# UNO-TH_Rev3e.net
KiCad netlist of a schematic drawn in Altium Designer
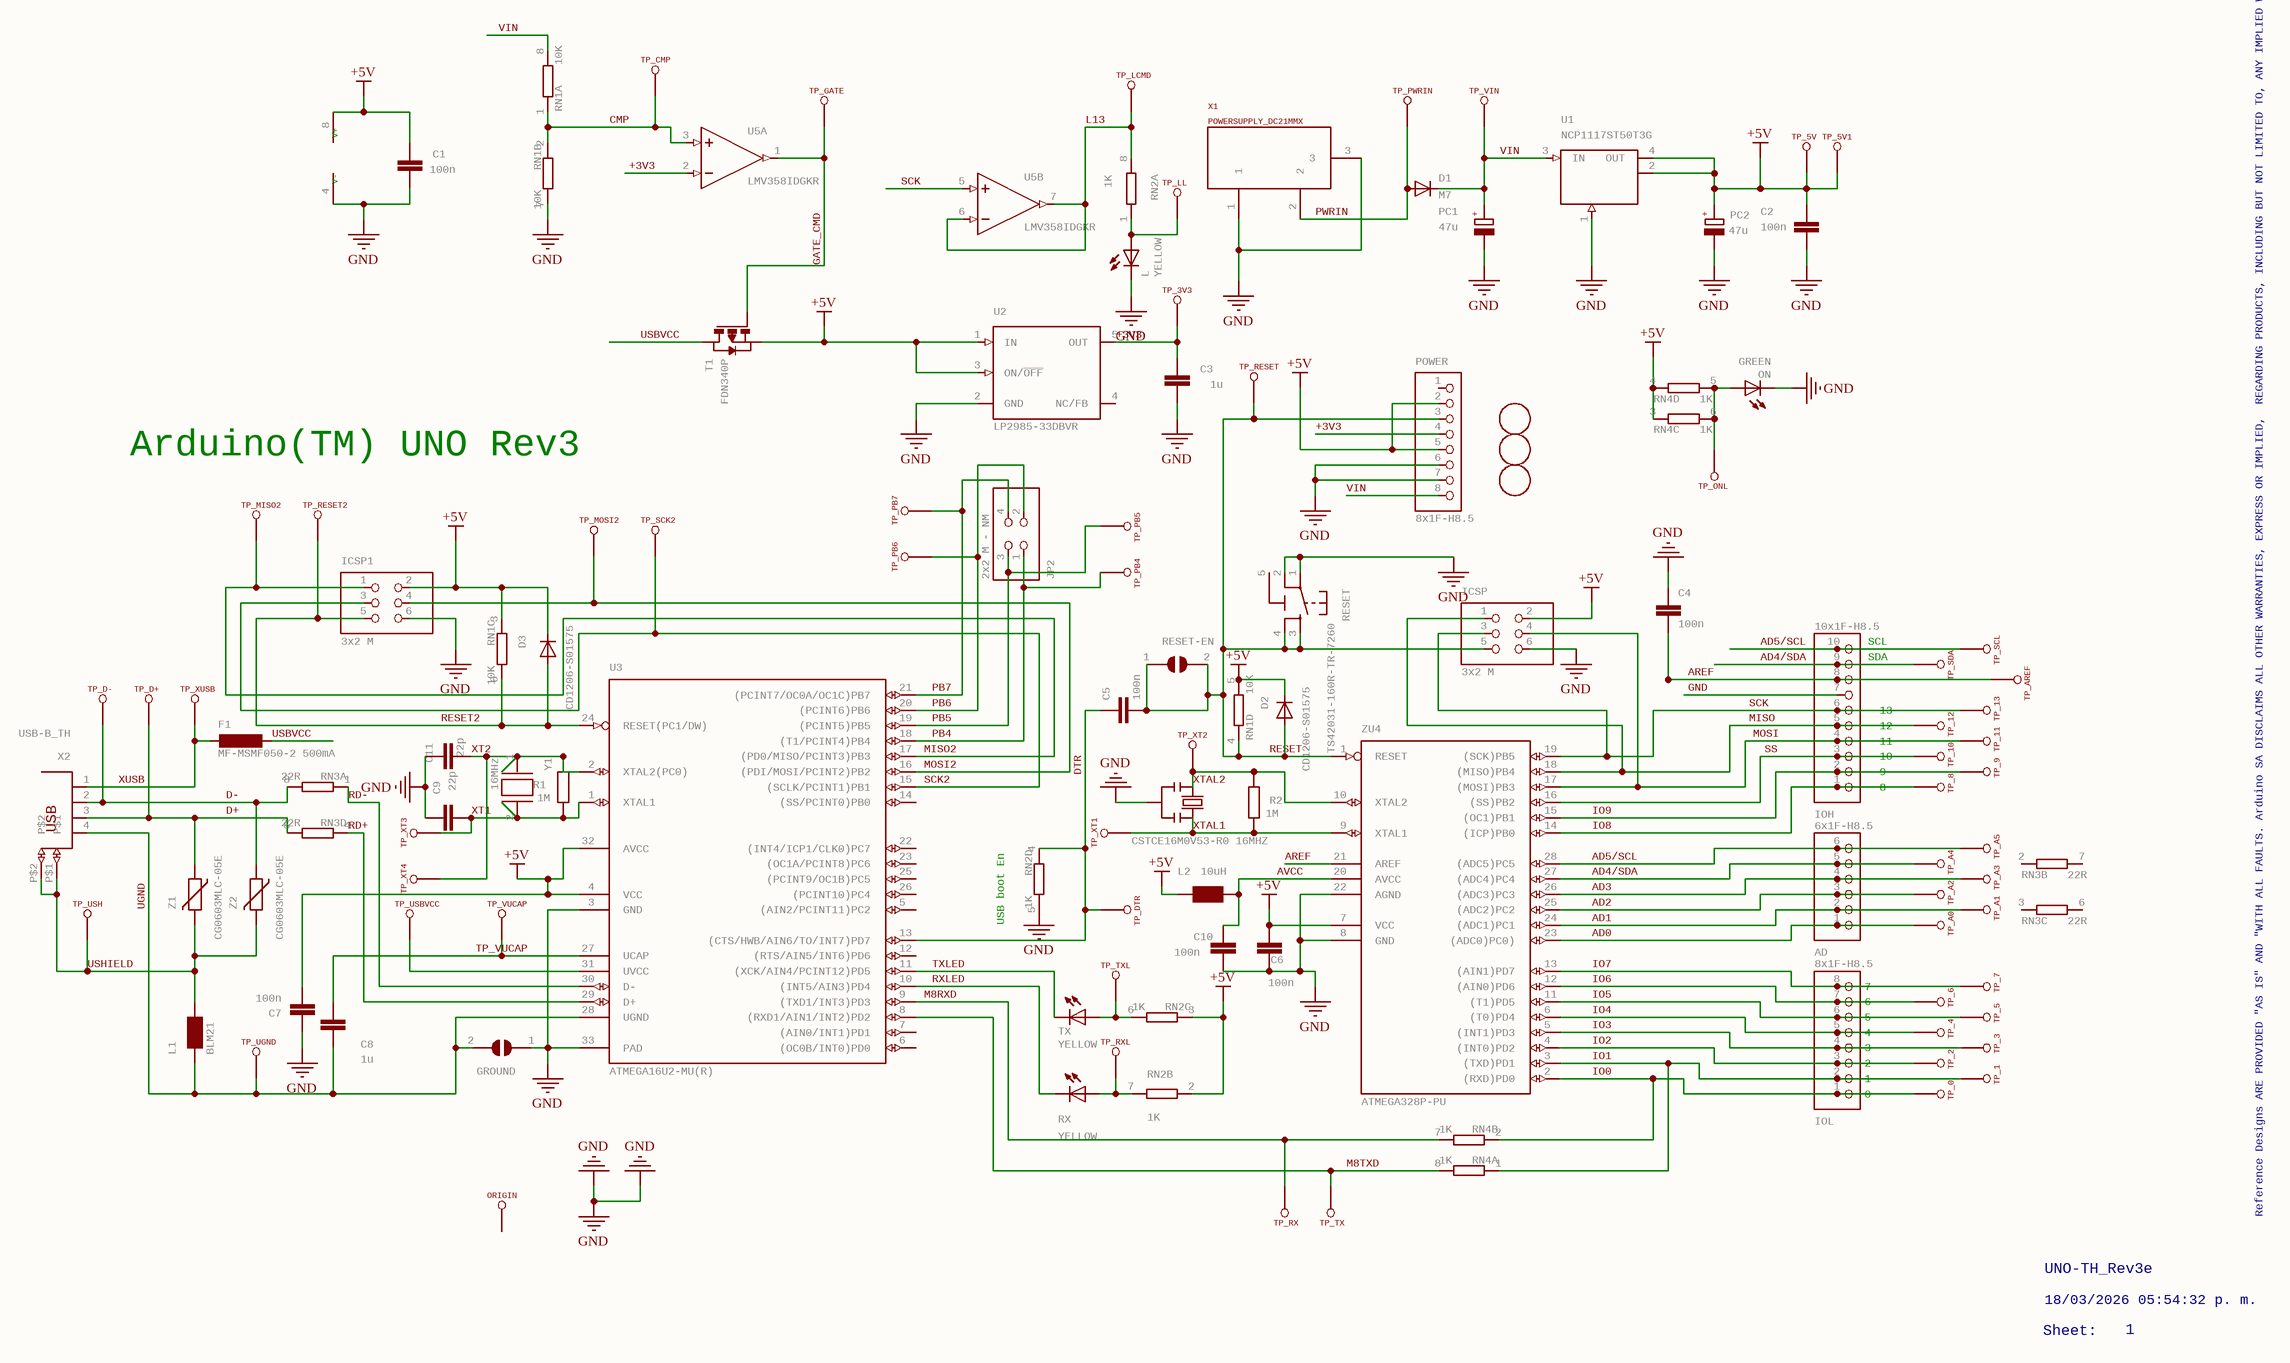
[diagram p0: UNO-TH_Rev3e.SchDoc]

(export (version "E")
  (design (tool "Eeschema 10.0.6"))
  (components
    (comp (ref "AD")
      (value "6x1F-H8.5")
      (footprint "1X06")
      (description "PIN HEADER")
      (libsource (lib "SmartPrj") (part "PINHD-1X6"))
    )
    (comp (ref "C1")
      (value "100n")
      (footprint "C0603-ROUND")
      (description "CAPACITOR, European symbol")
      (libsource (lib "") (part "C-EU0603-RND_2"))
    )
    (comp (ref "C2")
      (value "100n")
      (footprint "C0603-ROUND")
      (description "CAPACITOR, European symbol")
      (libsource (lib "") (part "C-EU0603-RND_1"))
    )
    (comp (ref "C3")
      (value "1u")
      (footprint "C0603-ROUND")
      (description "CAPACITOR, European symbol")
      (libsource (lib "") (part "C-EU0603-RND_2"))
    )
    (comp (ref "C4")
      (value "100n")
      (footprint "C0603-ROUND")
      (description "CAPACITOR, European symbol")
      (libsource (lib "SmartPrj") (part "C-EU0603-RND"))
    )
    (comp (ref "C5")
      (value "100n")
      (footprint "C0603-ROUND")
      (description "CAPACITOR, European symbol")
      (libsource (lib "") (part "C-EU0603-RND_2"))
    )
    (comp (ref "C6")
      (value "100n")
      (footprint "C0603-ROUND")
      (description "CAPACITOR, European symbol")
      (libsource (lib "") (part "C-EU0603-RND_1"))
    )
    (comp (ref "C7")
      (value "100n")
      (footprint "C0603-ROUND")
      (description "CAPACITOR, European symbol")
      (libsource (lib "") (part "C-EU0603-RND_3"))
    )
    (comp (ref "C8")
      (value "1u")
      (footprint "C0603-ROUND")
      (description "CAPACITOR, European symbol")
      (libsource (lib "") (part "C-EU0603-RND_3"))
    )
    (comp (ref "C9")
      (value "22p")
      (footprint "C0603-ROUND")
      (description "CAPACITOR, European symbol")
      (libsource (lib "SmartPrj") (part "C-EU0603-RND"))
    )
    (comp (ref "C10")
      (value "100n")
      (footprint "C0603-ROUND")
      (description "CAPACITOR, European symbol")
      (libsource (lib "") (part "C-EU0603-RND_1"))
    )
    (comp (ref "C11")
      (value "22p")
      (footprint "C0603-ROUND")
      (description "CAPACITOR, European symbol")
      (libsource (lib "SmartPrj") (part "C-EU0603-RND"))
    )
    (comp (ref "D1")
      (value "M7")
      (footprint "SMB")
      (description "DIODE")
      (libsource (lib "diode") (part "DIODE-SMB"))
    )
    (comp (ref "D2")
      (value "CD1206-S01575")
      (footprint "MINIMELF")
      (description "DIODE")
      (libsource (lib "diode") (part "DIODE-MINIMELF"))
    )
    (comp (ref "D3")
      (value "CD1206-S01575")
      (footprint "MINIMELF")
      (description "DIODE")
      (libsource (lib "diode") (part "DIODE-MINIMELF"))
    )
    (comp (ref "F1")
      (value "MF-MSMF050-2 500mA")
      (footprint "L1812")
      (description "INDUCTOR, European symbol")
      (libsource (lib "rcl") (part "L-EUL1812"))
    )
    (comp (ref "FD1")
      (value "FIDUCIALMOUNT")
      (footprint "FIDUCIA-MOUNT")
      (libsource (lib "SmartPrj") (part "FIDUCIALMOUNT"))
    )
    (comp (ref "FD2")
      (value "FIDUCIALMOUNT")
      (footprint "FIDUCIA-MOUNT")
      (libsource (lib "SmartPrj") (part "FIDUCIALMOUNT"))
    )
    (comp (ref "FD3")
      (value "FIDUCIALMOUNT")
      (footprint "FIDUCIA-MOUNT")
      (libsource (lib "SmartPrj") (part "FIDUCIALMOUNT"))
    )
    (comp (ref "GROUND")
      (value "SJ")
      (footprint "SJ")
      (description "SMD solder JUMPER")
      (libsource (lib "jumper") (part "SJ"))
    )
    (comp (ref "ICSP")
      (value "3x2 M")
      (footprint "2X03")
      (description "PIN HEADER")
      (libsource (lib "SmartPrj") (part "PINHD-2X3"))
    )
    (comp (ref "ICSP1")
      (value "3x2 M")
      (footprint "2X03")
      (description "PIN HEADER")
      (libsource (lib "SmartPrj") (part "PINHD-2X3"))
    )
    (comp (ref "IOH")
      (value "10x1F-H8.5")
      (footprint "1X10")
      (description "PIN HEADER")
      (libsource (lib "SmartPrj") (part "PINHD-1X10_ARD"))
    )
    (comp (ref "IOL")
      (value "8x1F-H8.5")
      (footprint "1X08")
      (description "PIN HEADER")
      (libsource (lib "SmartPrj") (part "PINHD-1X8"))
    )
    (comp (ref "JP2")
      (value "2x2 M - NM")
      (footprint "2X02")
      (description "PIN HEADER")
      (libsource (lib "SmartPrj") (part "PINHD-2X2"))
    )
    (comp (ref "L")
      (value "YELLOW")
      (footprint "CHIP-LED0805")
      (libsource (lib "led") (part "LEDCHIP-LED0805"))
    )
    (comp (ref "L1")
      (value "BLM21")
      (footprint "0805")
      (libsource (lib "wuerth-elektronik") (part "WE-CBF_0805"))
    )
    (comp (ref "L2")
      (value "10uH")
      (footprint "0805")
      (description "10uH 0805")
      (fields (field (name "PART_NUMBER") "CV201210-100K"))
      (libsource (lib "Induttanze") (part "0715_CV201210-100K"))
    )
    (comp (ref "ON")
      (value "GREEN")
      (footprint "CHIP-LED0805")
      (libsource (lib "led") (part "LEDCHIP-LED0805"))
    )
    (comp (ref "ORIGIN") (value "TP_SP") (footprint "TP-SP") (libsource (lib "SmartPrj") (part "TP_SP")))
    (comp (ref "PC1")
      (value "47u")
      (footprint "PANASONIC_D")
      (description "POLARIZED CAPACITOR, European symbol")
      (fields (field (name "+") "+"))
      (libsource (lib "rcl") (part "CPOL-EUD"))
    )
    (comp (ref "PC2")
      (value "47u")
      (footprint "PANASONIC_D")
      (description "POLARIZED CAPACITOR, European symbol")
      (fields (field (name "+") "+"))
      (libsource (lib "rcl") (part "CPOL-EUD"))
    )
    (comp (ref "POWER")
      (value "8x1F-H8.5")
      (footprint "1X08")
      (description "PIN HEADER")
      (libsource (lib "SmartPrj") (part "PINHD-1X8"))
    )
    (comp (ref "R1")
      (value "1M")
      (footprint "R0603-ROUND")
      (description "RESISTOR, European symbol")
      (libsource (lib "SmartPrj") (part "R-EU_R0603"))
    )
    (comp (ref "R2")
      (value "1M")
      (footprint "R0603-ROUND")
      (description "RESISTOR, European symbol")
      (libsource (lib "SmartPrj") (part "R-EU_R0603"))
    )
    (comp (ref "RESET")
      (value "TS42031-160R-TR-7260")
      (footprint "TS42")
      (description "TS42 Dongnan Electronics Tact switch VDC 12V - 50mA")
      (libsource (lib "SmartPrj") (part "TS42"))
    )
    (comp (ref "RESET-EN")
      (value "SJ")
      (footprint "SJ")
      (description "SMD solder JUMPER")
      (libsource (lib "jumper") (part "SJ"))
    )
    (comp (ref "RN1")
      (value "10K")
      (footprint "CAY16")
      (description "Array Chip Resistor   Source: RS Component / Phycomp")
      (libsource (lib "resistor-dil") (part "4R-NCAY16"))
    )
    (comp (ref "RN2")
      (value "1K")
      (footprint "CAY16")
      (description "Array Chip Resistor   Source: RS Component / Phycomp")
      (libsource (lib "resistor-dil") (part "4R-NCAY16"))
    )
    (comp (ref "RN3")
      (value "22R")
      (footprint "CAY16")
      (description "Array Chip Resistor   Source: RS Component / Phycomp")
      (libsource (lib "resistor-dil") (part "4R-NCAY16"))
    )
    (comp (ref "RN4")
      (value "1K")
      (footprint "CAY16")
      (description "Array Chip Resistor   Source: RS Component / Phycomp")
      (libsource (lib "resistor-dil") (part "4R-NCAY16"))
    )
    (comp (ref "RX")
      (value "YELLOW")
      (footprint "CHIP-LED0805")
      (libsource (lib "led") (part "LEDCHIP-LED0805"))
    )
    (comp (ref "T1")
      (value "FDN340P")
      (footprint "SOT-23")
      (description "MOS FET")
      (libsource (lib "zetex") (part "PMOSSOT23"))
    )
    (comp (ref "TP_0") (value "TP_SP") (footprint "TP-SP") (libsource (lib "SmartPrj") (part "TP_SP")))
    (comp (ref "TP_1") (value "TP_SP") (footprint "TP-SP") (libsource (lib "SmartPrj") (part "TP_SP")))
    (comp (ref "TP_2") (value "TP_SP") (footprint "TP-SP") (libsource (lib "SmartPrj") (part "TP_SP")))
    (comp (ref "TP_3") (value "TP_SP") (footprint "TP-SP") (libsource (lib "SmartPrj") (part "TP_SP")))
    (comp (ref "TP_3V3") (value "TP_SP") (footprint "TP-SP") (libsource (lib "SmartPrj") (part "TP_SP")))
    (comp (ref "TP_4") (value "TP_SP") (footprint "TP-SP") (libsource (lib "SmartPrj") (part "TP_SP")))
    (comp (ref "TP_5") (value "TP_SP") (footprint "TP-SP") (libsource (lib "SmartPrj") (part "TP_SP")))
    (comp (ref "TP_5V") (value "TP_SP") (footprint "TP-SP") (libsource (lib "SmartPrj") (part "TP_SP")))
    (comp (ref "TP_5V1") (value "TP_SP") (footprint "TP-SP") (libsource (lib "SmartPrj") (part "TP_SP")))
    (comp (ref "TP_6") (value "TP_SP") (footprint "TP-SP") (libsource (lib "SmartPrj") (part "TP_SP")))
    (comp (ref "TP_7") (value "TP_SP") (footprint "TP-SP") (libsource (lib "SmartPrj") (part "TP_SP")))
    (comp (ref "TP_8") (value "TP_SP") (footprint "TP-SP") (libsource (lib "SmartPrj") (part "TP_SP")))
    (comp (ref "TP_9") (value "TP_SP") (footprint "TP-SP") (libsource (lib "SmartPrj") (part "TP_SP")))
    (comp (ref "TP_10") (value "TP_SP") (footprint "TP-SP") (libsource (lib "SmartPrj") (part "TP_SP")))
    (comp (ref "TP_11") (value "TP_SP") (footprint "TP-SP") (libsource (lib "SmartPrj") (part "TP_SP")))
    (comp (ref "TP_12") (value "TP_SP") (footprint "TP-SP") (libsource (lib "SmartPrj") (part "TP_SP")))
    (comp (ref "TP_13") (value "TP_SP") (footprint "TP-SP") (libsource (lib "SmartPrj") (part "TP_SP")))
    (comp (ref "TP_A0") (value "TP_SP") (footprint "TP-SP") (libsource (lib "SmartPrj") (part "TP_SP")))
    (comp (ref "TP_A1") (value "TP_SP") (footprint "TP-SP") (libsource (lib "SmartPrj") (part "TP_SP")))
    (comp (ref "TP_A2") (value "TP_SP") (footprint "TP-SP") (libsource (lib "SmartPrj") (part "TP_SP")))
    (comp (ref "TP_A3") (value "TP_SP") (footprint "TP-SP") (libsource (lib "SmartPrj") (part "TP_SP")))
    (comp (ref "TP_A4") (value "TP_SP") (footprint "TP-SP") (libsource (lib "SmartPrj") (part "TP_SP")))
    (comp (ref "TP_A5") (value "TP_SP") (footprint "TP-SP") (libsource (lib "SmartPrj") (part "TP_SP")))
    (comp (ref "TP_AREF") (value "TP_SP") (footprint "TP-SP") (libsource (lib "SmartPrj") (part "TP_SP")))
    (comp (ref "TP_CMP") (value "TP_SP") (footprint "TP-SP") (libsource (lib "SmartPrj") (part "TP_SP")))
    (comp (ref "TP_D+") (value "TP_SP") (footprint "TP-SP") (libsource (lib "SmartPrj") (part "TP_SP")))
    (comp (ref "TP_D-") (value "TP_SP") (footprint "TP-SP") (libsource (lib "SmartPrj") (part "TP_SP")))
    (comp (ref "TP_DTR") (value "TP_SP") (footprint "TP-SP") (libsource (lib "SmartPrj") (part "TP_SP")))
    (comp (ref "TP_GATE") (value "TP_SP") (footprint "TP-SP") (libsource (lib "SmartPrj") (part "TP_SP")))
    (comp (ref "TP_LCMD") (value "TP_SP") (footprint "TP-SP") (libsource (lib "SmartPrj") (part "TP_SP")))
    (comp (ref "TP_LL") (value "TP_SP") (footprint "TP-SP") (libsource (lib "SmartPrj") (part "TP_SP")))
    (comp (ref "TP_MISO2") (value "TP_SP") (footprint "TP-SP") (libsource (lib "SmartPrj") (part "TP_SP")))
    (comp (ref "TP_MOSI2") (value "TP_SP") (footprint "TP-SP") (libsource (lib "SmartPrj") (part "TP_SP")))
    (comp (ref "TP_ONL") (value "TP_SP") (footprint "TP-SP") (libsource (lib "SmartPrj") (part "TP_SP")))
    (comp (ref "TP_PB4") (value "TP_SP") (footprint "TP-SP") (libsource (lib "SmartPrj") (part "TP_SP")))
    (comp (ref "TP_PB5") (value "TP_SP") (footprint "TP-SP") (libsource (lib "SmartPrj") (part "TP_SP")))
    (comp (ref "TP_PB6") (value "TP_SP") (footprint "TP-SP") (libsource (lib "SmartPrj") (part "TP_SP")))
    (comp (ref "TP_PB7") (value "TP_SP") (footprint "TP-SP") (libsource (lib "SmartPrj") (part "TP_SP")))
    (comp (ref "TP_PWRIN") (value "TP_SP") (footprint "TP-SP") (libsource (lib "SmartPrj") (part "TP_SP")))
    (comp (ref "TP_RESET") (value "TP_SP") (footprint "TP-SP") (libsource (lib "SmartPrj") (part "TP_SP")))
    (comp (ref "TP_RESET2") (value "TP_SP") (footprint "TP-SP") (libsource (lib "SmartPrj") (part "TP_SP")))
    (comp (ref "TP_RX") (value "TP_SP") (footprint "TP-SP") (libsource (lib "SmartPrj") (part "TP_SP")))
    (comp (ref "TP_RXL") (value "TP_SP") (footprint "TP-SP") (libsource (lib "SmartPrj") (part "TP_SP")))
    (comp (ref "TP_SCK2") (value "TP_SP") (footprint "TP-SP") (libsource (lib "SmartPrj") (part "TP_SP")))
    (comp (ref "TP_SCL") (value "TP_SP") (footprint "TP-SP") (libsource (lib "SmartPrj") (part "TP_SP")))
    (comp (ref "TP_SDA") (value "TP_SP") (footprint "TP-SP") (libsource (lib "SmartPrj") (part "TP_SP")))
    (comp (ref "TP_TX") (value "TP_SP") (footprint "TP-SP") (libsource (lib "SmartPrj") (part "TP_SP")))
    (comp (ref "TP_TXL") (value "TP_SP") (footprint "TP-SP") (libsource (lib "SmartPrj") (part "TP_SP")))
    (comp (ref "TP_UGND") (value "TP_SP") (footprint "TP-SP") (libsource (lib "SmartPrj") (part "TP_SP")))
    (comp (ref "TP_USBVCC") (value "TP_SP") (footprint "TP-SP") (libsource (lib "SmartPrj") (part "TP_SP")))
    (comp (ref "TP_USH") (value "TP_SP") (footprint "TP-SP") (libsource (lib "SmartPrj") (part "TP_SP")))
    (comp (ref "TP_VIN") (value "TP_SP") (footprint "TP-SP") (libsource (lib "SmartPrj") (part "TP_SP")))
    (comp (ref "TP_VUCAP") (value "TP_SP") (footprint "TP-SP") (libsource (lib "SmartPrj") (part "TP_SP")))
    (comp (ref "TP_XT1") (value "TP_SP") (footprint "TP-SP") (libsource (lib "SmartPrj") (part "TP_SP")))
    (comp (ref "TP_XT2") (value "TP_SP") (footprint "TP-SP") (libsource (lib "SmartPrj") (part "TP_SP")))
    (comp (ref "TP_XT3") (value "TP_SP") (footprint "TP-SP") (libsource (lib "SmartPrj") (part "TP_SP")))
    (comp (ref "TP_XT4") (value "TP_SP") (footprint "TP-SP") (libsource (lib "SmartPrj") (part "TP_SP")))
    (comp (ref "TP_XUSB") (value "TP_SP") (footprint "TP-SP") (libsource (lib "SmartPrj") (part "TP_SP")))
    (comp (ref "TX")
      (value "YELLOW")
      (footprint "CHIP-LED0805")
      (libsource (lib "led") (part "LEDCHIP-LED0805"))
    )
    (comp (ref "U1")
      (value "NCP1117ST50T3G")
      (footprint "SOT223")
      (libsource (lib "linear") (part "MC33269ST*"))
    )
    (comp (ref "U2")
      (value "LP2985-33DBVR")
      (footprint "SOT23-DBV")
      (libsource (lib "SmartPrj") (part "LP2985-XXDBVR"))
    )
    (comp (ref "U3")
      (value "ATMEGA16U2-MU(R)")
      (footprint "MLF32")
      (libsource (lib "SmartPrj") (part "ATMEGA16U2-MU"))
    )
    (comp (ref "U5")
      (value "LMV358IDGKR")
      (footprint "MSOP08")
      (fields (field (name "V+") "V+") (field (name "V-") "V-"))
      (libsource (lib "linear") (part "LMV358?*MM"))
    )
    (comp (ref "X1")
      (value "POWERSUPPLY_DC21MMX")
      (footprint "POWERSUPPLY_DC-21MM")
      (libsource (lib "SmartPrj") (part "POWERSUPPLY_DC21MMX"))
    )
    (comp (ref "X2")
      (value "USB-B_TH")
      (footprint "PN61729")
      (description "BERG USB connector")
      (fields (field (name "USB") "USB"))
      (libsource (lib "SmartPrj") (part "PN61729"))
    )
    (comp (ref "Y1")
      (value "16MHz")
      (footprint "QS")
      (description "CRYSTAL")
      (libsource (lib "SmartPrj") (part "XTAL/S"))
    )
    (comp (ref "Y2")
      (value "CSTCE16M0V53-R0 16MHZ")
      (footprint "RESONATOR")
      (libsource (lib "SmartPrj") (part "RESONATORMU"))
    )
    (comp (ref "Z1")
      (value "CG0603MLC-05E")
      (footprint "CT/CN0603")
      (description "VARISTOR")
      (libsource (lib "varistor") (part "VARISTORCN0603"))
    )
    (comp (ref "Z2")
      (value "CG0603MLC-05E")
      (footprint "CT/CN0603")
      (description "VARISTOR")
      (libsource (lib "varistor") (part "VARISTORCN0603"))
    )
    (comp (ref "ZU4")
      (value "ATMEGA328P-PU")
      (footprint "DIL28-3")
      (description "MICROCONTROLLER   4 Kbytes FLASH   128 bytes SRAM   256 bytes EEPROM   UART   6-channel 10 bit ADC")
      (libsource (lib "SmartPrj") (part "ATMEGA328P-PU"))
    )
  )
  (nets
    (net (code "1") (name "+5V") (class "Default")
      (node (ref "C1") (pin "2") (pinfunction "2_2") (pintype "passive"))
      (node (ref "C2") (pin "2") (pinfunction "2_2") (pintype "passive"))
      (node (ref "C6") (pin "2") (pinfunction "2_2") (pintype "passive"))
      (node (ref "C7") (pin "1") (pinfunction "1_1") (pintype "passive"))
      (node (ref "D2") (pin "C") (pinfunction "C_C") (pintype "passive"))
      (node (ref "D3") (pin "C") (pinfunction "C_C") (pintype "passive"))
      (node (ref "ICSP") (pin "2") (pinfunction "2_2") (pintype "passive"))
      (node (ref "ICSP1") (pin "2") (pinfunction "2_2") (pintype "passive"))
      (node (ref "L2") (pin "1") (pinfunction "1_1") (pintype "passive"))
      (node (ref "PC2") (pin "+") (pinfunction "+_+") (pintype "passive"))
      (node (ref "POWER") (pin "2") (pinfunction "2_2") (pintype "passive"))
      (node (ref "POWER") (pin "5") (pinfunction "5_5") (pintype "passive"))
      (node (ref "RN1") (pin "3") (pinfunction "1_3") (pintype "passive"))
      (node (ref "RN1") (pin "5") (pinfunction "2_5") (pintype "passive"))
      (node (ref "RN2") (pin "2") (pinfunction "1_2") (pintype "passive"))
      (node (ref "RN2") (pin "3") (pinfunction "1_3") (pintype "passive"))
      (node (ref "RN4") (pin "3") (pinfunction "1_3") (pintype "passive"))
      (node (ref "RN4") (pin "4") (pinfunction "1_4") (pintype "passive"))
      (node (ref "T1") (pin "2") (pinfunction "S_2") (pintype "passive"))
      (node (ref "TP_5V") (pin "X") (pinfunction "TESTP_X") (pintype "passive"))
      (node (ref "TP_5V1") (pin "X") (pinfunction "TESTP_X") (pintype "passive"))
      (node (ref "U1") (pin "2") (pinfunction "OUT_2") (pintype "passive"))
      (node (ref "U1") (pin "4") (pinfunction "OUT_4") (pintype "passive"))
      (node (ref "U2") (pin "1") (pinfunction "IN_1") (pintype "input"))
      (node (ref "U2") (pin "3") (pinfunction "ON/~{OFF}_3") (pintype "input"))
      (node (ref "U3") (pin "32") (pinfunction "AVCC_32") (pintype "power_in"))
      (node (ref "U3") (pin "4") (pinfunction "VCC_4") (pintype "power_in"))
      (node (ref "U5") (pin "8") (pinfunction "V+_8") (pintype "power_in"))
      (node (ref "ZU4") (pin "7") (pinfunction "VCC_7") (pintype "power_in"))
    )
    (net (code "2") (name "/+3V3") (class "Default")
      (node (ref "C3") (pin "2") (pinfunction "2_2") (pintype "passive"))
      (node (ref "POWER") (pin "4") (pinfunction "4_4") (pintype "passive"))
      (node (ref "TP_3V3") (pin "X") (pinfunction "TESTP_X") (pintype "passive"))
      (node (ref "U2") (pin "5") (pinfunction "OUT_5") (pintype "passive"))
      (node (ref "U5") (pin "2") (pinfunction "-IN_2") (pintype "input"))
    )
    (net (code "3") (name "/AD0") (class "Default")
      (node (ref "AD") (pin "1") (pinfunction "1_1") (pintype "passive"))
      (node (ref "TP_A0") (pin "X") (pinfunction "TESTP_X") (pintype "passive"))
      (node (ref "ZU4") (pin "23") (pinfunction "(ADC0)PC0)_23") (pintype "bidirectional"))
    )
    (net (code "4") (name "/AD1") (class "Default")
      (node (ref "AD") (pin "2") (pinfunction "2_2") (pintype "passive"))
      (node (ref "TP_A1") (pin "X") (pinfunction "TESTP_X") (pintype "passive"))
      (node (ref "ZU4") (pin "24") (pinfunction "(ADC1)PC1_24") (pintype "bidirectional"))
    )
    (net (code "5") (name "/AD2") (class "Default")
      (node (ref "AD") (pin "3") (pinfunction "3_3") (pintype "passive"))
      (node (ref "TP_A2") (pin "X") (pinfunction "TESTP_X") (pintype "passive"))
      (node (ref "ZU4") (pin "25") (pinfunction "(ADC2)PC2_25") (pintype "bidirectional"))
    )
    (net (code "6") (name "/AD3") (class "Default")
      (node (ref "AD") (pin "4") (pinfunction "4_4") (pintype "passive"))
      (node (ref "TP_A3") (pin "X") (pinfunction "TESTP_X") (pintype "passive"))
      (node (ref "ZU4") (pin "26") (pinfunction "(ADC3)PC3_26") (pintype "bidirectional"))
    )
    (net (code "7") (name "/AD4{slash}SDA") (class "Default")
      (node (ref "AD") (pin "5") (pinfunction "5_5") (pintype "passive"))
      (node (ref "IOH") (pin "9") (pinfunction "9_9") (pintype "passive"))
      (node (ref "TP_A4") (pin "X") (pinfunction "TESTP_X") (pintype "passive"))
      (node (ref "TP_SDA") (pin "X") (pinfunction "TESTP_X") (pintype "passive"))
      (node (ref "ZU4") (pin "27") (pinfunction "(ADC4)PC4_27") (pintype "bidirectional"))
    )
    (net (code "8") (name "/AD5{slash}SCL") (class "Default")
      (node (ref "AD") (pin "6") (pinfunction "6_6") (pintype "passive"))
      (node (ref "IOH") (pin "10") (pinfunction "10_10") (pintype "passive"))
      (node (ref "TP_A5") (pin "X") (pinfunction "TESTP_X") (pintype "passive"))
      (node (ref "TP_SCL") (pin "X") (pinfunction "TESTP_X") (pintype "passive"))
      (node (ref "ZU4") (pin "28") (pinfunction "(ADC5)PC5_28") (pintype "bidirectional"))
    )
    (net (code "9") (name "/AREF") (class "Default")
      (node (ref "C4") (pin "2") (pinfunction "2_2") (pintype "passive"))
      (node (ref "IOH") (pin "8") (pinfunction "8_8") (pintype "passive"))
      (node (ref "TP_AREF") (pin "X") (pinfunction "TESTP_X") (pintype "passive"))
      (node (ref "ZU4") (pin "21") (pinfunction "AREF_21") (pintype "passive"))
    )
    (net (code "10") (name "/AVCC") (class "Default")
      (node (ref "C10") (pin "2") (pinfunction "2_2") (pintype "passive"))
      (node (ref "L2") (pin "2") (pinfunction "2_2") (pintype "passive"))
      (node (ref "ZU4") (pin "20") (pinfunction "AVCC_20") (pintype "power_in"))
    )
    (net (code "11") (name "/CMP") (class "Default")
      (node (ref "RN1") (pin "1") (pinfunction "1_1") (pintype "passive"))
      (node (ref "RN1") (pin "2") (pinfunction "1_2") (pintype "passive"))
      (node (ref "TP_CMP") (pin "X") (pinfunction "TESTP_X") (pintype "passive"))
      (node (ref "U5") (pin "3") (pinfunction "+IN_3") (pintype "input"))
    )
    (net (code "12") (name "/D+") (class "Default")
      (node (ref "RN3") (pin "5") (pinfunction "2_5") (pintype "passive"))
      (node (ref "TP_D+") (pin "X") (pinfunction "TESTP_X") (pintype "passive"))
      (node (ref "X2") (pin "3") (pinfunction "3_3") (pintype "bidirectional"))
      (node (ref "Z1") (pin "1") (pinfunction "1_1") (pintype "passive"))
    )
    (net (code "13") (name "/D-") (class "Default")
      (node (ref "RN3") (pin "8") (pinfunction "2_8") (pintype "passive"))
      (node (ref "TP_D-") (pin "X") (pinfunction "TESTP_X") (pintype "passive"))
      (node (ref "X2") (pin "2") (pinfunction "2_2") (pintype "bidirectional"))
      (node (ref "Z2") (pin "1") (pinfunction "1_1") (pintype "passive"))
    )
    (net (code "14") (name "/DTR") (class "Default")
      (node (ref "C5") (pin "1") (pinfunction "1_1") (pintype "passive"))
      (node (ref "RN2") (pin "4") (pinfunction "1_4") (pintype "passive"))
      (node (ref "TP_DTR") (pin "X") (pinfunction "TESTP_X") (pintype "passive"))
      (node (ref "U3") (pin "13") (pinfunction "(CTS/HWB/AIN6/TO/INT7)PD7_13") (pintype "bidirectional"))
    )
    (net (code "15") (name "/GATE_CMD") (class "Default")
      (node (ref "T1") (pin "3") (pinfunction "G_3") (pintype "passive"))
      (node (ref "TP_GATE") (pin "X") (pinfunction "TESTP_X") (pintype "passive"))
      (node (ref "U5") (pin "1") (pinfunction "OUT_1") (pintype "output"))
    )
    (net (code "16") (name "/IO0") (class "Default")
      (node (ref "IOL") (pin "1") (pinfunction "1_1") (pintype "passive"))
      (node (ref "RN4") (pin "2") (pinfunction "1_2") (pintype "passive"))
      (node (ref "TP_0") (pin "X") (pinfunction "TESTP_X") (pintype "passive"))
      (node (ref "ZU4") (pin "2") (pinfunction "(RXD)PD0_2") (pintype "bidirectional"))
    )
    (net (code "17") (name "/IO1") (class "Default")
      (node (ref "IOL") (pin "2") (pinfunction "2_2") (pintype "passive"))
      (node (ref "RN4") (pin "1") (pinfunction "1_1") (pintype "passive"))
      (node (ref "TP_1") (pin "X") (pinfunction "TESTP_X") (pintype "passive"))
      (node (ref "ZU4") (pin "3") (pinfunction "(TXD)PD1_3") (pintype "bidirectional"))
    )
    (net (code "18") (name "/IO2") (class "Default")
      (node (ref "IOL") (pin "3") (pinfunction "3_3") (pintype "passive"))
      (node (ref "TP_2") (pin "X") (pinfunction "TESTP_X") (pintype "passive"))
      (node (ref "ZU4") (pin "4") (pinfunction "(INT0)PD2_4") (pintype "bidirectional"))
    )
    (net (code "19") (name "/IO3") (class "Default")
      (node (ref "IOL") (pin "4") (pinfunction "4_4") (pintype "passive"))
      (node (ref "TP_3") (pin "X") (pinfunction "TESTP_X") (pintype "passive"))
      (node (ref "ZU4") (pin "5") (pinfunction "(INT1)PD3_5") (pintype "bidirectional"))
    )
    (net (code "20") (name "/IO4") (class "Default")
      (node (ref "IOL") (pin "5") (pinfunction "5_5") (pintype "passive"))
      (node (ref "TP_4") (pin "X") (pinfunction "TESTP_X") (pintype "passive"))
      (node (ref "ZU4") (pin "6") (pinfunction "(T0)PD4_6") (pintype "bidirectional"))
    )
    (net (code "21") (name "/IO5") (class "Default")
      (node (ref "IOL") (pin "6") (pinfunction "6_6") (pintype "passive"))
      (node (ref "TP_5") (pin "X") (pinfunction "TESTP_X") (pintype "passive"))
      (node (ref "ZU4") (pin "11") (pinfunction "(T1)PD5_11") (pintype "bidirectional"))
    )
    (net (code "22") (name "/IO6") (class "Default")
      (node (ref "IOL") (pin "7") (pinfunction "7_7") (pintype "passive"))
      (node (ref "TP_6") (pin "X") (pinfunction "TESTP_X") (pintype "passive"))
      (node (ref "ZU4") (pin "12") (pinfunction "(AIN0)PD6_12") (pintype "bidirectional"))
    )
    (net (code "23") (name "/IO7") (class "Default")
      (node (ref "IOL") (pin "8") (pinfunction "8_8") (pintype "passive"))
      (node (ref "TP_7") (pin "X") (pinfunction "TESTP_X") (pintype "passive"))
      (node (ref "ZU4") (pin "13") (pinfunction "(AIN1)PD7_13") (pintype "bidirectional"))
    )
    (net (code "24") (name "/IO8") (class "Default")
      (node (ref "IOH") (pin "1") (pinfunction "1_1") (pintype "passive"))
      (node (ref "TP_8") (pin "X") (pinfunction "TESTP_X") (pintype "passive"))
      (node (ref "ZU4") (pin "14") (pinfunction "(ICP)PB0_14") (pintype "bidirectional"))
    )
    (net (code "25") (name "/IO9") (class "Default")
      (node (ref "IOH") (pin "2") (pinfunction "2_2") (pintype "passive"))
      (node (ref "TP_9") (pin "X") (pinfunction "TESTP_X") (pintype "passive"))
      (node (ref "ZU4") (pin "15") (pinfunction "(OC1)PB1_15") (pintype "bidirectional"))
    )
    (net (code "26") (name "/L13") (class "Default")
      (node (ref "RN2") (pin "8") (pinfunction "2_8") (pintype "passive"))
      (node (ref "TP_LCMD") (pin "X") (pinfunction "TESTP_X") (pintype "passive"))
      (node (ref "U5") (pin "6") (pinfunction "-IN_6") (pintype "input"))
      (node (ref "U5") (pin "7") (pinfunction "OUT_7") (pintype "output"))
    )
    (net (code "27") (name "/M8RXD") (class "Default")
      (node (ref "RN4") (pin "7") (pinfunction "2_7") (pintype "passive"))
      (node (ref "TP_RX") (pin "X") (pinfunction "TESTP_X") (pintype "passive"))
      (node (ref "U3") (pin "9") (pinfunction "(TXD1/INT3)PD3_9") (pintype "bidirectional"))
    )
    (net (code "28") (name "/M8TXD") (class "Default")
      (node (ref "RN4") (pin "8") (pinfunction "2_8") (pintype "passive"))
      (node (ref "TP_TX") (pin "X") (pinfunction "TESTP_X") (pintype "passive"))
      (node (ref "U3") (pin "8") (pinfunction "(RXD1/AIN1/INT2)PD2_8") (pintype "bidirectional"))
    )
    (net (code "29") (name "/MISO") (class "Default")
      (node (ref "ICSP") (pin "1") (pinfunction "1_1") (pintype "passive"))
      (node (ref "IOH") (pin "5") (pinfunction "5_5") (pintype "passive"))
      (node (ref "TP_12") (pin "X") (pinfunction "TESTP_X") (pintype "passive"))
      (node (ref "ZU4") (pin "18") (pinfunction "(MISO)PB4_18") (pintype "bidirectional"))
    )
    (net (code "30") (name "/MISO2") (class "Default")
      (node (ref "ICSP1") (pin "1") (pinfunction "1_1") (pintype "passive"))
      (node (ref "TP_MISO2") (pin "X") (pinfunction "TESTP_X") (pintype "passive"))
      (node (ref "U3") (pin "17") (pinfunction "(PD0/MISO/PCINT3)PB3_17") (pintype "bidirectional"))
    )
    (net (code "31") (name "/MOSI") (class "Default")
      (node (ref "ICSP") (pin "4") (pinfunction "4_4") (pintype "passive"))
      (node (ref "IOH") (pin "4") (pinfunction "4_4") (pintype "passive"))
      (node (ref "TP_11") (pin "X") (pinfunction "TESTP_X") (pintype "passive"))
      (node (ref "ZU4") (pin "17") (pinfunction "(MOSI)PB3_17") (pintype "bidirectional"))
    )
    (net (code "32") (name "/MOSI2") (class "Default")
      (node (ref "ICSP1") (pin "4") (pinfunction "4_4") (pintype "passive"))
      (node (ref "TP_MOSI2") (pin "X") (pinfunction "TESTP_X") (pintype "passive"))
      (node (ref "U3") (pin "16") (pinfunction "(PDI/MOSI/PCINT2)PB2_16") (pintype "bidirectional"))
    )
    (net (code "33") (name "/PB4") (class "Default")
      (node (ref "JP2") (pin "1") (pinfunction "1_1") (pintype "passive"))
      (node (ref "TP_PB4") (pin "X") (pinfunction "TESTP_X") (pintype "passive"))
      (node (ref "U3") (pin "18") (pinfunction "(T1/PCINT4)PB4_18") (pintype "bidirectional"))
    )
    (net (code "34") (name "/PB5") (class "Default")
      (node (ref "JP2") (pin "3") (pinfunction "3_3") (pintype "passive"))
      (node (ref "TP_PB5") (pin "X") (pinfunction "TESTP_X") (pintype "passive"))
      (node (ref "U3") (pin "19") (pinfunction "(PCINT5)PB5_19") (pintype "bidirectional"))
    )
    (net (code "35") (name "/PB6") (class "Default")
      (node (ref "JP2") (pin "2") (pinfunction "2_2") (pintype "passive"))
      (node (ref "TP_PB6") (pin "X") (pinfunction "TESTP_X") (pintype "passive"))
      (node (ref "U3") (pin "20") (pinfunction "(PCINT6)PB6_20") (pintype "bidirectional"))
    )
    (net (code "36") (name "/PB7") (class "Default")
      (node (ref "JP2") (pin "4") (pinfunction "4_4") (pintype "passive"))
      (node (ref "TP_PB7") (pin "X") (pinfunction "TESTP_X") (pintype "passive"))
      (node (ref "U3") (pin "21") (pinfunction "(PCINT7/OC0A/OC1C)PB7_21") (pintype "bidirectional"))
    )
    (net (code "37") (name "/PWRIN") (class "Default")
      (node (ref "D1") (pin "A") (pinfunction "A_A") (pintype "passive"))
      (node (ref "TP_PWRIN") (pin "X") (pinfunction "TESTP_X") (pintype "passive"))
      (node (ref "X1") (pin "2") (pinfunction "2_2") (pintype "power_in"))
    )
    (net (code "38") (name "/RD+") (class "Default")
      (node (ref "RN3") (pin "4") (pinfunction "1_4") (pintype "passive"))
      (node (ref "U3") (pin "29") (pinfunction "D+_29") (pintype "bidirectional"))
    )
    (net (code "39") (name "/RD-") (class "Default")
      (node (ref "RN3") (pin "1") (pinfunction "1_1") (pintype "passive"))
      (node (ref "U3") (pin "30") (pinfunction "D-_30") (pintype "bidirectional"))
    )
    (net (code "40") (name "/RESET") (class "Default")
      (node (ref "C5") (pin "2") (pinfunction "2_2") (pintype "passive"))
      (node (ref "D2") (pin "A") (pinfunction "A_A") (pintype "passive"))
      (node (ref "ICSP") (pin "5") (pinfunction "5_5") (pintype "passive"))
      (node (ref "POWER") (pin "3") (pinfunction "3_3") (pintype "passive"))
      (node (ref "RESET") (pin "3") (pinfunction "3_3") (pintype "passive"))
      (node (ref "RESET") (pin "4") (pinfunction "4_4") (pintype "passive"))
      (node (ref "RESET-EN") (pin "1") (pinfunction "1_1") (pintype "passive"))
      (node (ref "RESET-EN") (pin "2") (pinfunction "2_2") (pintype "passive"))
      (node (ref "RN1") (pin "4") (pinfunction "1_4") (pintype "passive"))
      (node (ref "TP_RESET") (pin "X") (pinfunction "TESTP_X") (pintype "passive"))
      (node (ref "ZU4") (pin "1") (pinfunction "RESET_1") (pintype "input"))
    )
    (net (code "41") (name "/RESET2") (class "Default")
      (node (ref "D3") (pin "A") (pinfunction "A_A") (pintype "passive"))
      (node (ref "ICSP1") (pin "5") (pinfunction "5_5") (pintype "passive"))
      (node (ref "RN1") (pin "6") (pinfunction "2_6") (pintype "passive"))
      (node (ref "TP_RESET2") (pin "X") (pinfunction "TESTP_X") (pintype "passive"))
      (node (ref "U3") (pin "24") (pinfunction "RESET(PC1/DW)_24") (pintype "input"))
    )
    (net (code "42") (name "/RXLED") (class "Default")
      (node (ref "RX") (pin "C") (pinfunction "C_C") (pintype "passive"))
      (node (ref "U3") (pin "10") (pinfunction "(INT5/AIN3)PD4_10") (pintype "bidirectional"))
    )
    (net (code "43") (name "/SCK") (class "Default")
      (node (ref "ICSP") (pin "3") (pinfunction "3_3") (pintype "passive"))
      (node (ref "IOH") (pin "6") (pinfunction "6_6") (pintype "passive"))
      (node (ref "TP_13") (pin "X") (pinfunction "TESTP_X") (pintype "passive"))
      (node (ref "U5") (pin "5") (pinfunction "+IN_5") (pintype "input"))
      (node (ref "ZU4") (pin "19") (pinfunction "(SCK)PB5_19") (pintype "bidirectional"))
    )
    (net (code "44") (name "/SCK2") (class "Default")
      (node (ref "ICSP1") (pin "3") (pinfunction "3_3") (pintype "passive"))
      (node (ref "TP_SCK2") (pin "X") (pinfunction "TESTP_X") (pintype "passive"))
      (node (ref "U3") (pin "15") (pinfunction "(SCLK/PCINT1)PB1_15") (pintype "bidirectional"))
    )
    (net (code "45") (name "/SS") (class "Default")
      (node (ref "IOH") (pin "3") (pinfunction "3_3") (pintype "passive"))
      (node (ref "TP_10") (pin "X") (pinfunction "TESTP_X") (pintype "passive"))
      (node (ref "ZU4") (pin "16") (pinfunction "(SS)PB2_16") (pintype "bidirectional"))
    )
    (net (code "46") (name "/TP_VUCAP") (class "Default")
      (node (ref "C8") (pin "1") (pinfunction "1_1") (pintype "passive"))
      (node (ref "TP_VUCAP") (pin "X") (pinfunction "TESTP_X") (pintype "passive"))
      (node (ref "U3") (pin "27") (pinfunction "UCAP_27") (pintype "passive"))
    )
    (net (code "47") (name "/TXLED") (class "Default")
      (node (ref "TX") (pin "C") (pinfunction "C_C") (pintype "passive"))
      (node (ref "U3") (pin "11") (pinfunction "(XCK/AIN4/PCINT12)PD5_11") (pintype "bidirectional"))
    )
    (net (code "48") (name "/UGND") (class "Default")
      (node (ref "C8") (pin "2") (pinfunction "2_2") (pintype "passive"))
      (node (ref "GROUND") (pin "2") (pinfunction "2_2") (pintype "passive"))
      (node (ref "L1") (pin "1") (pinfunction "1_1") (pintype "passive"))
      (node (ref "TP_UGND") (pin "X") (pinfunction "TESTP_X") (pintype "passive"))
      (node (ref "U3") (pin "28") (pinfunction "UGND_28") (pintype "power_in"))
      (node (ref "X2") (pin "4") (pinfunction "4_4") (pintype "bidirectional"))
    )
    (net (code "49") (name "/USBVCC") (class "Default")
      (node (ref "F1") (pin "1") (pinfunction "1_1") (pintype "passive"))
      (node (ref "T1") (pin "1") (pinfunction "D_1") (pintype "passive"))
    )
    (net (code "50") (name "/USHIELD") (class "Default")
      (node (ref "L1") (pin "2") (pinfunction "2_2") (pintype "passive"))
      (node (ref "TP_USH") (pin "X") (pinfunction "TESTP_X") (pintype "passive"))
      (node (ref "X2") (pin "P$1") (pinfunction "P$1_P$1") (pintype "bidirectional"))
      (node (ref "X2") (pin "P$2") (pinfunction "P$2_P$2") (pintype "bidirectional"))
      (node (ref "Z1") (pin "2") (pinfunction "2_2") (pintype "passive"))
      (node (ref "Z2") (pin "2") (pinfunction "2_2") (pintype "passive"))
    )
    (net (code "51") (name "/VIN") (class "Default")
      (node (ref "D1") (pin "C") (pinfunction "C_C") (pintype "passive"))
      (node (ref "PC1") (pin "+") (pinfunction "+_+") (pintype "passive"))
      (node (ref "POWER") (pin "8") (pinfunction "8_8") (pintype "passive"))
      (node (ref "RN1") (pin "8") (pinfunction "2_8") (pintype "passive"))
      (node (ref "TP_VIN") (pin "X") (pinfunction "TESTP_X") (pintype "passive"))
      (node (ref "U1") (pin "3") (pinfunction "IN_3") (pintype "input"))
    )
    (net (code "52") (name "/XT1") (class "Default")
      (node (ref "C9") (pin "1") (pinfunction "1_1") (pintype "passive"))
      (node (ref "R1") (pin "1") (pinfunction "1_1") (pintype "passive"))
      (node (ref "TP_XT3") (pin "X") (pinfunction "TESTP_X") (pintype "passive"))
      (node (ref "U3") (pin "1") (pinfunction "XTAL1_1") (pintype "bidirectional"))
      (node (ref "Y1") (pin "2") (pinfunction "2_2") (pintype "passive"))
    )
    (net (code "53") (name "/XT2") (class "Default")
      (node (ref "C11") (pin "1") (pinfunction "1_1") (pintype "passive"))
      (node (ref "R1") (pin "2") (pinfunction "2_2") (pintype "passive"))
      (node (ref "TP_XT4") (pin "X") (pinfunction "TESTP_X") (pintype "passive"))
      (node (ref "U3") (pin "2") (pinfunction "XTAL2(PC0)_2") (pintype "bidirectional"))
      (node (ref "Y1") (pin "1") (pinfunction "1_1") (pintype "passive"))
    )
    (net (code "54") (name "/XTAL1") (class "Default")
      (node (ref "R2") (pin "1") (pinfunction "1_1") (pintype "passive"))
      (node (ref "TP_XT1") (pin "X") (pinfunction "TESTP_X") (pintype "passive"))
      (node (ref "Y2") (pin "3") (pinfunction "3_3") (pintype "passive"))
      (node (ref "ZU4") (pin "9") (pinfunction "XTAL1_9") (pintype "bidirectional"))
    )
    (net (code "55") (name "/XTAL2") (class "Default")
      (node (ref "R2") (pin "2") (pinfunction "2_2") (pintype "passive"))
      (node (ref "TP_XT2") (pin "X") (pinfunction "TESTP_X") (pintype "passive"))
      (node (ref "Y2") (pin "1") (pinfunction "1_1") (pintype "passive"))
      (node (ref "ZU4") (pin "10") (pinfunction "XTAL2_10") (pintype "bidirectional"))
    )
    (net (code "56") (name "/XUSB") (class "Default")
      (node (ref "F1") (pin "2") (pinfunction "2_2") (pintype "passive"))
      (node (ref "TP_XUSB") (pin "X") (pinfunction "TESTP_X") (pintype "passive"))
      (node (ref "X2") (pin "1") (pinfunction "1_1") (pintype "bidirectional"))
    )
    (net (code "57") (name "GND") (class "Default")
      (node (ref "C1") (pin "1") (pinfunction "1_1") (pintype "passive"))
      (node (ref "C10") (pin "1") (pinfunction "1_1") (pintype "passive"))
      (node (ref "C11") (pin "2") (pinfunction "2_2") (pintype "passive"))
      (node (ref "C2") (pin "1") (pinfunction "1_1") (pintype "passive"))
      (node (ref "C3") (pin "1") (pinfunction "1_1") (pintype "passive"))
      (node (ref "C4") (pin "1") (pinfunction "1_1") (pintype "passive"))
      (node (ref "C6") (pin "1") (pinfunction "1_1") (pintype "passive"))
      (node (ref "C7") (pin "2") (pinfunction "2_2") (pintype "passive"))
      (node (ref "C9") (pin "2") (pinfunction "2_2") (pintype "passive"))
      (node (ref "GROUND") (pin "1") (pinfunction "1_1") (pintype "passive"))
      (node (ref "ICSP") (pin "6") (pinfunction "6_6") (pintype "passive"))
      (node (ref "ICSP1") (pin "6") (pinfunction "6_6") (pintype "passive"))
      (node (ref "IOH") (pin "7") (pinfunction "7_7") (pintype "passive"))
      (node (ref "L") (pin "C") (pinfunction "C_C") (pintype "passive"))
      (node (ref "ON") (pin "C") (pinfunction "C_C") (pintype "passive"))
      (node (ref "PC1") (pin "-") (pinfunction "-_-") (pintype "passive"))
      (node (ref "PC2") (pin "-") (pinfunction "-_-") (pintype "passive"))
      (node (ref "POWER") (pin "6") (pinfunction "6_6") (pintype "passive"))
      (node (ref "POWER") (pin "7") (pinfunction "7_7") (pintype "passive"))
      (node (ref "RESET") (pin "1") (pinfunction "1_1") (pintype "passive"))
      (node (ref "RESET") (pin "2") (pinfunction "2_2") (pintype "passive"))
      (node (ref "RN1") (pin "7") (pinfunction "2_7") (pintype "passive"))
      (node (ref "RN2") (pin "5") (pinfunction "2_5") (pintype "passive"))
      (node (ref "U1") (pin "1") (pinfunction "GND/ADJ_1") (pintype "input"))
      (node (ref "U2") (pin "2") (pinfunction "GND_2") (pintype "power_in"))
      (node (ref "U3") (pin "3") (pinfunction "GND_3") (pintype "power_in"))
      (node (ref "U3") (pin "33") (pinfunction "PAD_33") (pintype "power_in"))
      (node (ref "U5") (pin "4") (pinfunction "V-_4") (pintype "power_in"))
      (node (ref "X1") (pin "1") (pinfunction "1_1") (pintype "power_in"))
      (node (ref "X1") (pin "3") (pinfunction "3_3") (pintype "power_in"))
      (node (ref "Y2") (pin "2") (pinfunction "2_2") (pintype "passive"))
      (node (ref "ZU4") (pin "22") (pinfunction "AGND_22") (pintype "power_in"))
      (node (ref "ZU4") (pin "8") (pinfunction "GND_8") (pintype "power_in"))
    )
    (net (code "58") (name "Net-(RN2B-2)") (class "Default")
      (node (ref "RN2") (pin "7") (pinfunction "2_7") (pintype "passive"))
      (node (ref "RX") (pin "A") (pinfunction "A_A") (pintype "passive"))
      (node (ref "TP_RXL") (pin "X") (pinfunction "TESTP_X") (pintype "passive"))
    )
    (net (code "59") (name "Net-(RN2C-2)") (class "Default")
      (node (ref "RN2") (pin "6") (pinfunction "2_6") (pintype "passive"))
      (node (ref "TP_TXL") (pin "X") (pinfunction "TESTP_X") (pintype "passive"))
      (node (ref "TX") (pin "A") (pinfunction "A_A") (pintype "passive"))
    )
    (net (code "60") (name "Net-(RN4C-2)") (class "Default")
      (node (ref "ON") (pin "A") (pinfunction "A_A") (pintype "passive"))
      (node (ref "RN4") (pin "5") (pinfunction "2_5") (pintype "passive"))
      (node (ref "RN4") (pin "6") (pinfunction "2_6") (pintype "passive"))
      (node (ref "TP_ONL") (pin "X") (pinfunction "TESTP_X") (pintype "passive"))
    )
    (net (code "61") (name "Net-(TP_LL-TESTP)") (class "Default")
      (node (ref "L") (pin "A") (pinfunction "A_A") (pintype "passive"))
      (node (ref "RN2") (pin "1") (pinfunction "1_1") (pintype "passive"))
      (node (ref "TP_LL") (pin "X") (pinfunction "TESTP_X") (pintype "passive"))
    )
    (net (code "62") (name "Net-(TP_USBVCC-TESTP)") (class "Default")
      (node (ref "TP_USBVCC") (pin "X") (pinfunction "TESTP_X") (pintype "passive"))
      (node (ref "U3") (pin "31") (pinfunction "UVCC_31") (pintype "power_in"))
    )
    (net (code "63") (name "unconnected-(ORIGIN-TESTP-PadX)") (class "Default")
      (node (ref "ORIGIN") (pin "X") (pinfunction "TESTP_X") (pintype "passive"))
    )
    (net (code "64") (name "unconnected-(POWER-Pad1)") (class "Default")
      (node (ref "POWER") (pin "1") (pinfunction "1_1") (pintype "passive"))
    )
    (net (code "65") (name "unconnected-(RESET-5-GND-Pad5)") (class "Default")
      (node (ref "RESET") (pin "5") (pinfunction "5-GND_5") (pintype "power_in"))
    )
    (net (code "66") (name "unconnected-(RN3B-1-Pad2)") (class "Default")
      (node (ref "RN3") (pin "2") (pinfunction "1_2") (pintype "passive"))
    )
    (net (code "67") (name "unconnected-(RN3B-2-Pad7)") (class "Default")
      (node (ref "RN3") (pin "7") (pinfunction "2_7") (pintype "passive"))
    )
    (net (code "68") (name "unconnected-(RN3C-1-Pad3)") (class "Default")
      (node (ref "RN3") (pin "3") (pinfunction "1_3") (pintype "passive"))
    )
    (net (code "69") (name "unconnected-(RN3C-2-Pad6)") (class "Default")
      (node (ref "RN3") (pin "6") (pinfunction "2_6") (pintype "passive"))
    )
    (net (code "70") (name "unconnected-(U2-NC{slash}FB-Pad4)") (class "Default")
      (node (ref "U2") (pin "4") (pinfunction "NC/FB_4") (pintype "passive"))
    )
    (net (code "71") (name "unconnected-(U3-(AIN0{slash}INT1)PD1-Pad7)") (class "Default")
      (node (ref "U3") (pin "7") (pinfunction "(AIN0/INT1)PD1_7") (pintype "bidirectional"))
    )
    (net (code "72") (name "unconnected-(U3-(AIN2{slash}PCINT11)PC2-Pad5)") (class "Default")
      (node (ref "U3") (pin "5") (pinfunction "(AIN2/PCINT11)PC2_5") (pintype "bidirectional"))
    )
    (net (code "73") (name "unconnected-(U3-(INT4{slash}ICP1{slash}CLK0)PC7-Pad22)") (class "Default")
      (node (ref "U3") (pin "22") (pinfunction "(INT4/ICP1/CLK0)PC7_22") (pintype "bidirectional"))
    )
    (net (code "74") (name "unconnected-(U3-(OC0B{slash}INT0)PD0-Pad6)") (class "Default")
      (node (ref "U3") (pin "6") (pinfunction "(OC0B/INT0)PD0_6") (pintype "bidirectional"))
    )
    (net (code "75") (name "unconnected-(U3-(OC1A{slash}PCINT8)PC6-Pad23)") (class "Default")
      (node (ref "U3") (pin "23") (pinfunction "(OC1A/PCINT8)PC6_23") (pintype "bidirectional"))
    )
    (net (code "76") (name "unconnected-(U3-(PCINT9{slash}OC1B)PC5-Pad25)") (class "Default")
      (node (ref "U3") (pin "25") (pinfunction "(PCINT9/OC1B)PC5_25") (pintype "bidirectional"))
    )
    (net (code "77") (name "unconnected-(U3-(PCINT10)PC4-Pad26)") (class "Default")
      (node (ref "U3") (pin "26") (pinfunction "(PCINT10)PC4_26") (pintype "bidirectional"))
    )
    (net (code "78") (name "unconnected-(U3-(RTS{slash}AIN5{slash}INT6)PD6-Pad12)") (class "Default")
      (node (ref "U3") (pin "12") (pinfunction "(RTS/AIN5/INT6)PD6_12") (pintype "bidirectional"))
    )
    (net (code "79") (name "unconnected-(U3-(SS{slash}PCINT0)PB0-Pad14)") (class "Default")
      (node (ref "U3") (pin "14") (pinfunction "(SS/PCINT0)PB0_14") (pintype "bidirectional"))
    )
  )
)
